# PCB4Layer.net
KiCad netlist of a schematic drawn in Altium Designer
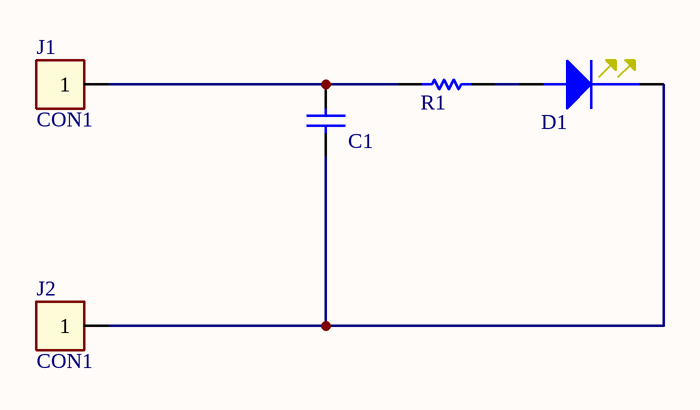
[diagram p0: PCB4Layer.SchDoc]

(export (version "E")
  (design (tool "Eeschema 10.0.6"))
  (components
    (comp (ref "C1")
      (value "1u")
      (footprint "SM/IPC/C_1206")
      (description "CAP CER 1UF 100V X7R 1206")
      (fields (field (name "PART NUMBER") "CAP_1u_10%_100V_1206_X7R") (field (name "TOLERANCE") "10%"))
      (libsource (lib "PCB-Lib") (part "CAP_NP"))
    )
    (comp (ref "D1")
      (value "YELLOW LED")
      (footprint "RH/LED_T1")
      (fields (field (name "PART NUMBER") "LED_YEL_T1"))
      (libsource (lib "PCB-Lib") (part "LED_YEL"))
    )
    (comp (ref "J1")
      (value "CON1")
      (footprint "BATTERYCONTACT")
      (description "Battery Contact Springs")
      (libsource (lib "PCB-Lib") (part "CON1"))
    )
    (comp (ref "J2")
      (value "CON1")
      (footprint "BATTERYCONTACT")
      (description "Battery Contact Springs")
      (libsource (lib "PCB-Lib") (part "CON1"))
    )
    (comp (ref "R1")
      (value "1k")
      (footprint "SM/IPC/R_1206")
      (description "RES SMD 1K OHM 1% 1/4W 1206")
      (fields (field (name "PART NUMBER") "R_1k_1%_1206") (field (name "TOLERANCE") "1%"))
      (libsource (lib "PCB-Lib") (part "R"))
    )
  )
  (nets
    (net (code "1") (name "Net-(C1-Pad1)") (class "Default")
      (node (ref "C1") (pin "1") (pinfunction "1_1") (pintype "passive"))
      (node (ref "D1") (pin "C") (pinfunction "C_C") (pintype "passive"))
      (node (ref "J2") (pin "1") (pinfunction "1_1") (pintype "passive"))
    )
    (net (code "2") (name "Net-(C1-Pad2)") (class "Default")
      (node (ref "C1") (pin "2") (pinfunction "2_2") (pintype "passive"))
      (node (ref "J1") (pin "1") (pinfunction "1_1") (pintype "passive"))
      (node (ref "R1") (pin "1") (pinfunction "1_1") (pintype "passive"))
    )
    (net (code "3") (name "Net-(D1-PadA)") (class "Default")
      (node (ref "D1") (pin "A") (pinfunction "A_A") (pintype "passive"))
      (node (ref "R1") (pin "2") (pinfunction "2_2") (pintype "passive"))
    )
  )
)
